# picotouch_smd.net
KiCad netlist of a schematic drawn in EAGLE
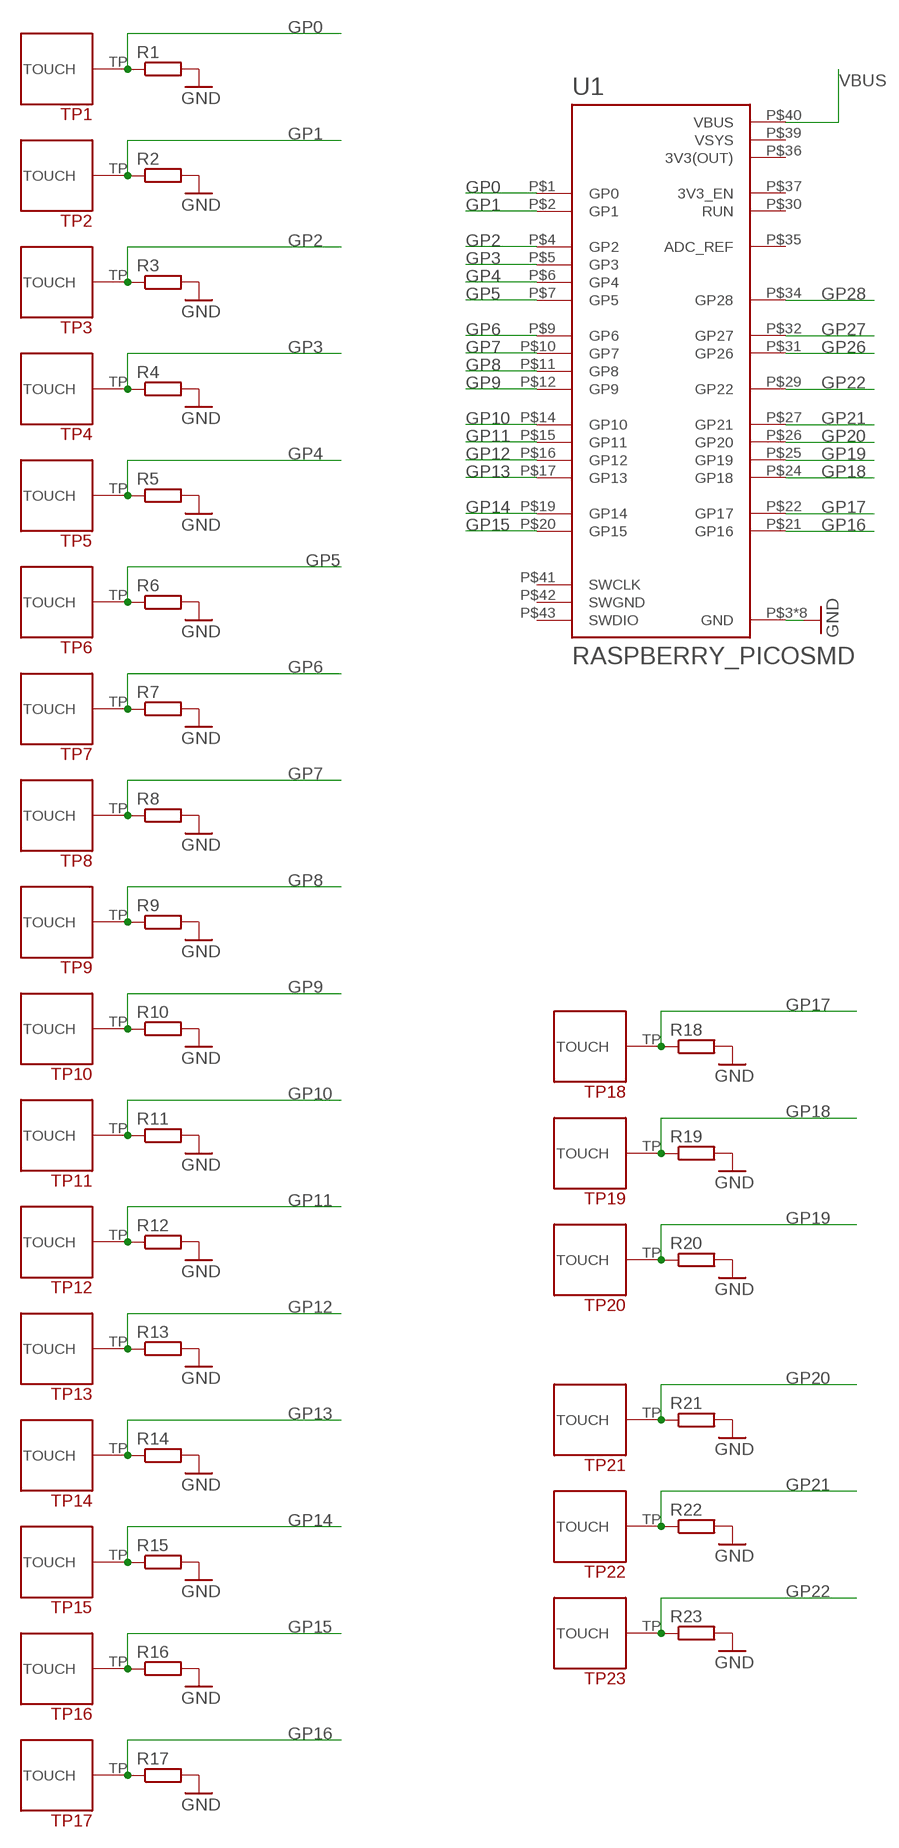
[diagram p0: schematic, sheet 1]

(export (version "E")
  (design (tool "Eeschema 10.0.6"))
  (components
    (comp (ref "R1")
      (value "R-EU_R0805")
      (footprint "eagle-import:R0805")
      (libsource (lib "eagle-import") (part "R-EU_R0805"))
    )
    (comp (ref "R2")
      (value "R-EU_R0805")
      (footprint "eagle-import:R0805")
      (libsource (lib "eagle-import") (part "R-EU_R0805"))
    )
    (comp (ref "R3")
      (value "R-EU_R0805")
      (footprint "eagle-import:R0805")
      (libsource (lib "eagle-import") (part "R-EU_R0805"))
    )
    (comp (ref "R4")
      (value "R-EU_R0805")
      (footprint "eagle-import:R0805")
      (libsource (lib "eagle-import") (part "R-EU_R0805"))
    )
    (comp (ref "R5")
      (value "R-EU_R0805")
      (footprint "eagle-import:R0805")
      (libsource (lib "eagle-import") (part "R-EU_R0805"))
    )
    (comp (ref "R6")
      (value "R-EU_R0805")
      (footprint "eagle-import:R0805")
      (libsource (lib "eagle-import") (part "R-EU_R0805"))
    )
    (comp (ref "R7")
      (value "R-EU_R0805")
      (footprint "eagle-import:R0805")
      (libsource (lib "eagle-import") (part "R-EU_R0805"))
    )
    (comp (ref "R8")
      (value "R-EU_R0805")
      (footprint "eagle-import:R0805")
      (libsource (lib "eagle-import") (part "R-EU_R0805"))
    )
    (comp (ref "R9")
      (value "R-EU_R0805")
      (footprint "eagle-import:R0805")
      (libsource (lib "eagle-import") (part "R-EU_R0805"))
    )
    (comp (ref "R10")
      (value "R-EU_R0805")
      (footprint "eagle-import:R0805")
      (libsource (lib "eagle-import") (part "R-EU_R0805"))
    )
    (comp (ref "R11")
      (value "R-EU_R0805")
      (footprint "eagle-import:R0805")
      (libsource (lib "eagle-import") (part "R-EU_R0805"))
    )
    (comp (ref "R12")
      (value "R-EU_R0805")
      (footprint "eagle-import:R0805")
      (libsource (lib "eagle-import") (part "R-EU_R0805"))
    )
    (comp (ref "R13")
      (value "R-EU_R0805")
      (footprint "eagle-import:R0805")
      (libsource (lib "eagle-import") (part "R-EU_R0805"))
    )
    (comp (ref "R14")
      (value "R-EU_R0805")
      (footprint "eagle-import:R0805")
      (libsource (lib "eagle-import") (part "R-EU_R0805"))
    )
    (comp (ref "R15")
      (value "R-EU_R0805")
      (footprint "eagle-import:R0805")
      (libsource (lib "eagle-import") (part "R-EU_R0805"))
    )
    (comp (ref "R16")
      (value "R-EU_R0805")
      (footprint "eagle-import:R0805")
      (libsource (lib "eagle-import") (part "R-EU_R0805"))
    )
    (comp (ref "R17")
      (value "R-EU_R0805")
      (footprint "eagle-import:R0805")
      (libsource (lib "eagle-import") (part "R-EU_R0805"))
    )
    (comp (ref "R18")
      (value "R-EU_R0805")
      (footprint "eagle-import:R0805")
      (libsource (lib "eagle-import") (part "R-EU_R0805"))
    )
    (comp (ref "R19")
      (value "R-EU_R0805")
      (footprint "eagle-import:R0805")
      (libsource (lib "eagle-import") (part "R-EU_R0805"))
    )
    (comp (ref "R20")
      (value "R-EU_R0805")
      (footprint "eagle-import:R0805")
      (libsource (lib "eagle-import") (part "R-EU_R0805"))
    )
    (comp (ref "R21")
      (value "R-EU_R0805")
      (footprint "eagle-import:R0805")
      (libsource (lib "eagle-import") (part "R-EU_R0805"))
    )
    (comp (ref "R22")
      (value "R-EU_R0805")
      (footprint "eagle-import:R0805")
      (libsource (lib "eagle-import") (part "R-EU_R0805"))
    )
    (comp (ref "R23")
      (value "R-EU_R0805")
      (footprint "eagle-import:R0805")
      (libsource (lib "eagle-import") (part "R-EU_R0805"))
    )
    (comp (ref "TP1")
      (value "TOUCHPADA")
      (footprint "eagle-import:TOUCHPADA")
      (libsource (lib "eagle-import") (part "TOUCHPADA"))
    )
    (comp (ref "TP2")
      (value "TOUCHPADA")
      (footprint "eagle-import:TOUCHPADA")
      (libsource (lib "eagle-import") (part "TOUCHPADA"))
    )
    (comp (ref "TP3")
      (value "TOUCHPADA")
      (footprint "eagle-import:TOUCHPADA")
      (libsource (lib "eagle-import") (part "TOUCHPADA"))
    )
    (comp (ref "TP4")
      (value "TOUCHPADA")
      (footprint "eagle-import:TOUCHPADA")
      (libsource (lib "eagle-import") (part "TOUCHPADA"))
    )
    (comp (ref "TP5")
      (value "TOUCHPADA")
      (footprint "eagle-import:TOUCHPADA")
      (libsource (lib "eagle-import") (part "TOUCHPADA"))
    )
    (comp (ref "TP6")
      (value "TOUCHPADA")
      (footprint "eagle-import:TOUCHPADA")
      (libsource (lib "eagle-import") (part "TOUCHPADA"))
    )
    (comp (ref "TP7")
      (value "TOUCHPADA")
      (footprint "eagle-import:TOUCHPADA")
      (libsource (lib "eagle-import") (part "TOUCHPADA"))
    )
    (comp (ref "TP8")
      (value "TOUCHPADA")
      (footprint "eagle-import:TOUCHPADA")
      (libsource (lib "eagle-import") (part "TOUCHPADA"))
    )
    (comp (ref "TP9")
      (value "TOUCHPADA")
      (footprint "eagle-import:TOUCHPADA")
      (libsource (lib "eagle-import") (part "TOUCHPADA"))
    )
    (comp (ref "TP10")
      (value "TOUCHPADA")
      (footprint "eagle-import:TOUCHPADA")
      (libsource (lib "eagle-import") (part "TOUCHPADA"))
    )
    (comp (ref "TP11")
      (value "TOUCHPADA")
      (footprint "eagle-import:TOUCHPADA")
      (libsource (lib "eagle-import") (part "TOUCHPADA"))
    )
    (comp (ref "TP12")
      (value "TOUCHPADA")
      (footprint "eagle-import:TOUCHPADA")
      (libsource (lib "eagle-import") (part "TOUCHPADA"))
    )
    (comp (ref "TP13")
      (value "TOUCHPADA")
      (footprint "eagle-import:TOUCHPADA")
      (libsource (lib "eagle-import") (part "TOUCHPADA"))
    )
    (comp (ref "TP14")
      (value "TOUCHPADA")
      (footprint "eagle-import:TOUCHPADA")
      (libsource (lib "eagle-import") (part "TOUCHPADA"))
    )
    (comp (ref "TP15")
      (value "TOUCHPADA")
      (footprint "eagle-import:TOUCHPADA")
      (libsource (lib "eagle-import") (part "TOUCHPADA"))
    )
    (comp (ref "TP16")
      (value "TOUCHPADA")
      (footprint "eagle-import:TOUCHPADA")
      (libsource (lib "eagle-import") (part "TOUCHPADA"))
    )
    (comp (ref "TP17")
      (value "TOUCHPADA")
      (footprint "eagle-import:TOUCHPADA")
      (libsource (lib "eagle-import") (part "TOUCHPADA"))
    )
    (comp (ref "TP18")
      (value "TOUCHPADB")
      (footprint "eagle-import:TOUCHPADB")
      (libsource (lib "eagle-import") (part "TOUCHPADB"))
    )
    (comp (ref "TP19")
      (value "TOUCHPADB")
      (footprint "eagle-import:TOUCHPADB")
      (libsource (lib "eagle-import") (part "TOUCHPADB"))
    )
    (comp (ref "TP20")
      (value "TOUCHPADB")
      (footprint "eagle-import:TOUCHPADB")
      (libsource (lib "eagle-import") (part "TOUCHPADB"))
    )
    (comp (ref "TP21")
      (value "TOUCHPADB")
      (footprint "eagle-import:TOUCHPADB")
      (libsource (lib "eagle-import") (part "TOUCHPADB"))
    )
    (comp (ref "TP22")
      (value "TOUCHPADB")
      (footprint "eagle-import:TOUCHPADB")
      (libsource (lib "eagle-import") (part "TOUCHPADB"))
    )
    (comp (ref "TP23")
      (value "TOUCHPADB")
      (footprint "eagle-import:TOUCHPADB")
      (libsource (lib "eagle-import") (part "TOUCHPADB"))
    )
    (comp (ref "U1")
      (value "RASPBERRY_PICOSMD")
      (footprint "eagle-import:PICO-PKG-SMD")
      (libsource (lib "eagle-import") (part "RASPBERRY_PICOSMD"))
    )
  )
  (nets
    (net (code "1") (name "/3V3(OUT)") (class "Default")
      (node (ref "U1") (pin "P$36") (pinfunction "3V3(OUT)_P$36") (pintype "power_in"))
    )
    (net (code "2") (name "/GP0") (class "Default")
      (node (ref "R1") (pin "1") (pinfunction "1_1") (pintype "passive"))
      (node (ref "TP1") (pin "TP") (pinfunction "TOUCH_TP") (pintype "bidirectional"))
      (node (ref "U1") (pin "P$1") (pinfunction "GP0_P$1") (pintype "bidirectional"))
    )
    (net (code "3") (name "/GP1") (class "Default")
      (node (ref "R2") (pin "1") (pinfunction "1_1") (pintype "passive"))
      (node (ref "TP2") (pin "TP") (pinfunction "TOUCH_TP") (pintype "bidirectional"))
      (node (ref "U1") (pin "P$2") (pinfunction "GP1_P$2") (pintype "bidirectional"))
    )
    (net (code "4") (name "/GP2") (class "Default")
      (node (ref "R3") (pin "1") (pinfunction "1_1") (pintype "passive"))
      (node (ref "TP3") (pin "TP") (pinfunction "TOUCH_TP") (pintype "bidirectional"))
      (node (ref "U1") (pin "P$4") (pinfunction "GP2_P$4") (pintype "bidirectional"))
    )
    (net (code "5") (name "/GP3") (class "Default")
      (node (ref "R4") (pin "1") (pinfunction "1_1") (pintype "passive"))
      (node (ref "TP4") (pin "TP") (pinfunction "TOUCH_TP") (pintype "bidirectional"))
      (node (ref "U1") (pin "P$5") (pinfunction "GP3_P$5") (pintype "bidirectional"))
    )
    (net (code "6") (name "/GP4") (class "Default")
      (node (ref "R5") (pin "1") (pinfunction "1_1") (pintype "passive"))
      (node (ref "TP5") (pin "TP") (pinfunction "TOUCH_TP") (pintype "bidirectional"))
      (node (ref "U1") (pin "P$6") (pinfunction "GP4_P$6") (pintype "bidirectional"))
    )
    (net (code "7") (name "/GP5") (class "Default")
      (node (ref "R6") (pin "1") (pinfunction "1_1") (pintype "passive"))
      (node (ref "TP6") (pin "TP") (pinfunction "TOUCH_TP") (pintype "bidirectional"))
      (node (ref "U1") (pin "P$7") (pinfunction "GP5_P$7") (pintype "bidirectional"))
    )
    (net (code "8") (name "/GP6") (class "Default")
      (node (ref "R7") (pin "1") (pinfunction "1_1") (pintype "passive"))
      (node (ref "TP7") (pin "TP") (pinfunction "TOUCH_TP") (pintype "bidirectional"))
      (node (ref "U1") (pin "P$9") (pinfunction "GP6_P$9") (pintype "bidirectional"))
    )
    (net (code "9") (name "/GP7") (class "Default")
      (node (ref "R8") (pin "1") (pinfunction "1_1") (pintype "passive"))
      (node (ref "TP8") (pin "TP") (pinfunction "TOUCH_TP") (pintype "bidirectional"))
      (node (ref "U1") (pin "P$10") (pinfunction "GP7_P$10") (pintype "bidirectional"))
    )
    (net (code "10") (name "/GP8") (class "Default")
      (node (ref "R9") (pin "1") (pinfunction "1_1") (pintype "passive"))
      (node (ref "TP9") (pin "TP") (pinfunction "TOUCH_TP") (pintype "bidirectional"))
      (node (ref "U1") (pin "P$11") (pinfunction "GP8_P$11") (pintype "bidirectional"))
    )
    (net (code "11") (name "/GP9") (class "Default")
      (node (ref "R10") (pin "1") (pinfunction "1_1") (pintype "passive"))
      (node (ref "TP10") (pin "TP") (pinfunction "TOUCH_TP") (pintype "bidirectional"))
      (node (ref "U1") (pin "P$12") (pinfunction "GP9_P$12") (pintype "bidirectional"))
    )
    (net (code "12") (name "/GP10") (class "Default")
      (node (ref "R11") (pin "1") (pinfunction "1_1") (pintype "passive"))
      (node (ref "TP11") (pin "TP") (pinfunction "TOUCH_TP") (pintype "bidirectional"))
      (node (ref "U1") (pin "P$14") (pinfunction "GP10_P$14") (pintype "bidirectional"))
    )
    (net (code "13") (name "/GP11") (class "Default")
      (node (ref "R12") (pin "1") (pinfunction "1_1") (pintype "passive"))
      (node (ref "TP12") (pin "TP") (pinfunction "TOUCH_TP") (pintype "bidirectional"))
      (node (ref "U1") (pin "P$15") (pinfunction "GP11_P$15") (pintype "bidirectional"))
    )
    (net (code "14") (name "/GP12") (class "Default")
      (node (ref "R13") (pin "1") (pinfunction "1_1") (pintype "passive"))
      (node (ref "TP13") (pin "TP") (pinfunction "TOUCH_TP") (pintype "bidirectional"))
      (node (ref "U1") (pin "P$16") (pinfunction "GP12_P$16") (pintype "bidirectional"))
    )
    (net (code "15") (name "/GP13") (class "Default")
      (node (ref "R14") (pin "1") (pinfunction "1_1") (pintype "passive"))
      (node (ref "TP14") (pin "TP") (pinfunction "TOUCH_TP") (pintype "bidirectional"))
      (node (ref "U1") (pin "P$17") (pinfunction "GP13_P$17") (pintype "bidirectional"))
    )
    (net (code "16") (name "/GP14") (class "Default")
      (node (ref "R15") (pin "1") (pinfunction "1_1") (pintype "passive"))
      (node (ref "TP15") (pin "TP") (pinfunction "TOUCH_TP") (pintype "bidirectional"))
      (node (ref "U1") (pin "P$19") (pinfunction "GP14_P$19") (pintype "bidirectional"))
    )
    (net (code "17") (name "/GP15") (class "Default")
      (node (ref "R16") (pin "1") (pinfunction "1_1") (pintype "passive"))
      (node (ref "TP16") (pin "TP") (pinfunction "TOUCH_TP") (pintype "bidirectional"))
      (node (ref "U1") (pin "P$20") (pinfunction "GP15_P$20") (pintype "bidirectional"))
    )
    (net (code "18") (name "/GP16") (class "Default")
      (node (ref "R17") (pin "1") (pinfunction "1_1") (pintype "passive"))
      (node (ref "TP17") (pin "TP") (pinfunction "TOUCH_TP") (pintype "bidirectional"))
      (node (ref "U1") (pin "P$21") (pinfunction "GP16_P$21") (pintype "bidirectional"))
    )
    (net (code "19") (name "/GP17") (class "Default")
      (node (ref "R18") (pin "1") (pinfunction "1_1") (pintype "passive"))
      (node (ref "TP18") (pin "TP") (pinfunction "TOUCH_TP") (pintype "bidirectional"))
      (node (ref "U1") (pin "P$22") (pinfunction "GP17_P$22") (pintype "bidirectional"))
    )
    (net (code "20") (name "/GP18") (class "Default")
      (node (ref "R19") (pin "1") (pinfunction "1_1") (pintype "passive"))
      (node (ref "TP19") (pin "TP") (pinfunction "TOUCH_TP") (pintype "bidirectional"))
      (node (ref "U1") (pin "P$24") (pinfunction "GP18_P$24") (pintype "bidirectional"))
    )
    (net (code "21") (name "/GP19") (class "Default")
      (node (ref "R20") (pin "1") (pinfunction "1_1") (pintype "passive"))
      (node (ref "TP20") (pin "TP") (pinfunction "TOUCH_TP") (pintype "bidirectional"))
      (node (ref "U1") (pin "P$25") (pinfunction "GP19_P$25") (pintype "bidirectional"))
    )
    (net (code "22") (name "/GP20") (class "Default")
      (node (ref "R21") (pin "1") (pinfunction "1_1") (pintype "passive"))
      (node (ref "TP21") (pin "TP") (pinfunction "TOUCH_TP") (pintype "bidirectional"))
      (node (ref "U1") (pin "P$26") (pinfunction "GP20_P$26") (pintype "bidirectional"))
    )
    (net (code "23") (name "/GP21") (class "Default")
      (node (ref "R22") (pin "1") (pinfunction "1_1") (pintype "passive"))
      (node (ref "TP22") (pin "TP") (pinfunction "TOUCH_TP") (pintype "bidirectional"))
      (node (ref "U1") (pin "P$27") (pinfunction "GP21_P$27") (pintype "bidirectional"))
    )
    (net (code "24") (name "/GP22") (class "Default")
      (node (ref "R23") (pin "1") (pinfunction "1_1") (pintype "passive"))
      (node (ref "TP23") (pin "TP") (pinfunction "TOUCH_TP") (pintype "bidirectional"))
      (node (ref "U1") (pin "P$29") (pinfunction "GP22_P$29") (pintype "bidirectional"))
    )
    (net (code "25") (name "/GP26") (class "Default")
      (node (ref "U1") (pin "P$31") (pinfunction "GP26_P$31") (pintype "bidirectional"))
    )
    (net (code "26") (name "/GP27") (class "Default")
      (node (ref "U1") (pin "P$32") (pinfunction "GP27_P$32") (pintype "bidirectional"))
    )
    (net (code "27") (name "/GP28") (class "Default")
      (node (ref "U1") (pin "P$34") (pinfunction "GP28_P$34") (pintype "bidirectional"))
    )
    (net (code "28") (name "/SWGND") (class "Default")
      (node (ref "U1") (pin "P$42") (pinfunction "SWGND_P$42") (pintype "power_in"))
    )
    (net (code "29") (name "/VBUS") (class "Default")
      (node (ref "U1") (pin "P$40") (pinfunction "VBUS_P$40") (pintype "power_in"))
    )
    (net (code "30") (name "/VSYS") (class "Default")
      (node (ref "U1") (pin "P$39") (pinfunction "VSYS_P$39") (pintype "power_in"))
    )
    (net (code "31") (name "GND") (class "Default")
      (node (ref "R1") (pin "2") (pinfunction "2_2") (pintype "passive"))
      (node (ref "R10") (pin "2") (pinfunction "2_2") (pintype "passive"))
      (node (ref "R11") (pin "2") (pinfunction "2_2") (pintype "passive"))
      (node (ref "R12") (pin "2") (pinfunction "2_2") (pintype "passive"))
      (node (ref "R13") (pin "2") (pinfunction "2_2") (pintype "passive"))
      (node (ref "R14") (pin "2") (pinfunction "2_2") (pintype "passive"))
      (node (ref "R15") (pin "2") (pinfunction "2_2") (pintype "passive"))
      (node (ref "R16") (pin "2") (pinfunction "2_2") (pintype "passive"))
      (node (ref "R17") (pin "2") (pinfunction "2_2") (pintype "passive"))
      (node (ref "R18") (pin "2") (pinfunction "2_2") (pintype "passive"))
      (node (ref "R19") (pin "2") (pinfunction "2_2") (pintype "passive"))
      (node (ref "R2") (pin "2") (pinfunction "2_2") (pintype "passive"))
      (node (ref "R20") (pin "2") (pinfunction "2_2") (pintype "passive"))
      (node (ref "R21") (pin "2") (pinfunction "2_2") (pintype "passive"))
      (node (ref "R22") (pin "2") (pinfunction "2_2") (pintype "passive"))
      (node (ref "R23") (pin "2") (pinfunction "2_2") (pintype "passive"))
      (node (ref "R3") (pin "2") (pinfunction "2_2") (pintype "passive"))
      (node (ref "R4") (pin "2") (pinfunction "2_2") (pintype "passive"))
      (node (ref "R5") (pin "2") (pinfunction "2_2") (pintype "passive"))
      (node (ref "R6") (pin "2") (pinfunction "2_2") (pintype "passive"))
      (node (ref "R7") (pin "2") (pinfunction "2_2") (pintype "passive"))
      (node (ref "R8") (pin "2") (pinfunction "2_2") (pintype "passive"))
      (node (ref "R9") (pin "2") (pinfunction "2_2") (pintype "passive"))
      (node (ref "U1") (pin "P$13") (pinfunction "GND_P$13") (pintype "power_in"))
      (node (ref "U1") (pin "P$18") (pinfunction "GND_P$18") (pintype "power_in"))
      (node (ref "U1") (pin "P$23") (pinfunction "GND_P$23") (pintype "power_in"))
      (node (ref "U1") (pin "P$28") (pinfunction "GND_P$28") (pintype "power_in"))
      (node (ref "U1") (pin "P$3") (pinfunction "GND_P$3") (pintype "power_in"))
      (node (ref "U1") (pin "P$33") (pinfunction "GND_P$33") (pintype "power_in"))
      (node (ref "U1") (pin "P$38") (pinfunction "GND_P$38") (pintype "power_in"))
      (node (ref "U1") (pin "P$8") (pinfunction "GND_P$8") (pintype "power_in"))
    )
    (net (code "32") (name "unconnected-(U1-3V3_EN-PadP$37)") (class "Default")
      (node (ref "U1") (pin "P$37") (pinfunction "3V3_EN_P$37") (pintype "input"))
    )
    (net (code "33") (name "unconnected-(U1-ADC_REF-PadP$35)") (class "Default")
      (node (ref "U1") (pin "P$35") (pinfunction "ADC_REF_P$35") (pintype "input"))
    )
    (net (code "34") (name "unconnected-(U1-RUN-PadP$30)") (class "Default")
      (node (ref "U1") (pin "P$30") (pinfunction "RUN_P$30") (pintype "input"))
    )
    (net (code "35") (name "unconnected-(U1-SWCLK-PadP$41)") (class "Default")
      (node (ref "U1") (pin "P$41") (pinfunction "SWCLK_P$41") (pintype "input"))
    )
    (net (code "36") (name "unconnected-(U1-SWDIO-PadP$43)") (class "Default")
      (node (ref "U1") (pin "P$43") (pinfunction "SWDIO_P$43") (pintype "bidirectional"))
    )
  )
)
